# DC_RF_ADDER_single_channel.net
KiCad netlist of a schematic drawn in EAGLE
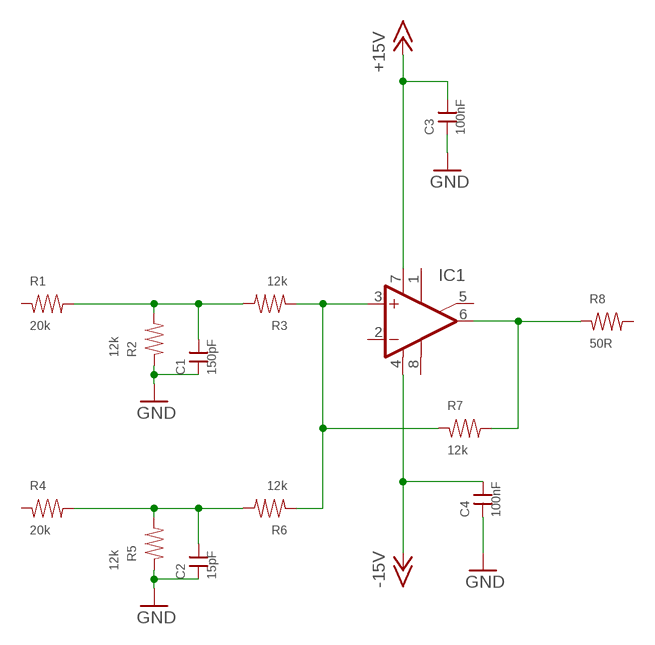
[diagram p0: schematic, sheet 1]

(export (version "E")
  (design (tool "Eeschema 10.0.6"))
  (components
    (comp (ref "C1")
      (value "150pF")
      (footprint "eagle-import:0603")
      (libsource (lib "eagle-import") (part "CAP0603"))
    )
    (comp (ref "C2")
      (value "15pF")
      (footprint "eagle-import:0603")
      (libsource (lib "eagle-import") (part "CAP0603"))
    )
    (comp (ref "C3")
      (value "100nF")
      (footprint "eagle-import:0603")
      (libsource (lib "eagle-import") (part "CAP0603"))
    )
    (comp (ref "C4")
      (value "100nF")
      (footprint "eagle-import:0603")
      (libsource (lib "eagle-import") (part "CAP0603"))
    )
    (comp (ref "IC1")
      (value "OPAMP-SO")
      (footprint "eagle-import:SO08")
      (libsource (lib "eagle-import") (part "OPAMP-SO"))
    )
    (comp (ref "R1")
      (value "20k")
      (footprint "eagle-import:0603")
      (libsource (lib "eagle-import") (part "RES0603"))
    )
    (comp (ref "R2")
      (value "12k")
      (footprint "eagle-import:0603")
      (libsource (lib "eagle-import") (part "RES0603"))
    )
    (comp (ref "R3")
      (value "12k")
      (footprint "eagle-import:0603")
      (libsource (lib "eagle-import") (part "RES0603"))
    )
    (comp (ref "R4")
      (value "20k")
      (footprint "eagle-import:0603")
      (libsource (lib "eagle-import") (part "RES0603"))
    )
    (comp (ref "R5")
      (value "12k")
      (footprint "eagle-import:0603")
      (libsource (lib "eagle-import") (part "RES0603"))
    )
    (comp (ref "R6")
      (value "12k")
      (footprint "eagle-import:0603")
      (libsource (lib "eagle-import") (part "RES0603"))
    )
    (comp (ref "R7")
      (value "12k")
      (footprint "eagle-import:0603")
      (libsource (lib "eagle-import") (part "RES0603"))
    )
    (comp (ref "R8")
      (value "50R")
      (footprint "eagle-import:0603")
      (libsource (lib "eagle-import") (part "RES0603"))
    )
  )
  (nets
    (net (code "1") (name "+15V") (class "Default")
      (node (ref "C3") (pin "2") (pinfunction "P$2_2") (pintype "passive"))
      (node (ref "IC1") (pin "7") (pinfunction "V+_7") (pintype "power_in"))
    )
    (net (code "2") (name "-15V") (class "Default")
      (node (ref "C4") (pin "2") (pinfunction "P$2_2") (pintype "passive"))
      (node (ref "IC1") (pin "4") (pinfunction "V-_4") (pintype "power_in"))
    )
    (net (code "3") (name "GND") (class "Default")
      (node (ref "C1") (pin "1") (pinfunction "P$1_1") (pintype "passive"))
      (node (ref "C2") (pin "1") (pinfunction "P$1_1") (pintype "passive"))
      (node (ref "C3") (pin "1") (pinfunction "P$1_1") (pintype "passive"))
      (node (ref "C4") (pin "1") (pinfunction "P$1_1") (pintype "passive"))
      (node (ref "R2") (pin "1") (pinfunction "P$1_1") (pintype "passive"))
      (node (ref "R5") (pin "1") (pinfunction "P$1_1") (pintype "passive"))
    )
    (net (code "4") (name "Net-(C1-P$2)") (class "Default")
      (node (ref "C1") (pin "2") (pinfunction "P$2_2") (pintype "passive"))
      (node (ref "R1") (pin "2") (pinfunction "P$2_2") (pintype "passive"))
      (node (ref "R2") (pin "2") (pinfunction "P$2_2") (pintype "passive"))
      (node (ref "R3") (pin "2") (pinfunction "P$2_2") (pintype "passive"))
    )
    (net (code "5") (name "Net-(C2-P$2)") (class "Default")
      (node (ref "C2") (pin "2") (pinfunction "P$2_2") (pintype "passive"))
      (node (ref "R4") (pin "2") (pinfunction "P$2_2") (pintype "passive"))
      (node (ref "R5") (pin "2") (pinfunction "P$2_2") (pintype "passive"))
      (node (ref "R6") (pin "2") (pinfunction "P$2_2") (pintype "passive"))
    )
    (net (code "6") (name "Net-(IC1-+IN)") (class "Default")
      (node (ref "IC1") (pin "3") (pinfunction "+IN_3") (pintype "input"))
      (node (ref "R3") (pin "1") (pinfunction "P$1_1") (pintype "passive"))
      (node (ref "R6") (pin "1") (pinfunction "P$1_1") (pintype "passive"))
      (node (ref "R7") (pin "1") (pinfunction "P$1_1") (pintype "passive"))
    )
    (net (code "7") (name "Net-(IC1-OUT)") (class "Default")
      (node (ref "IC1") (pin "6") (pinfunction "OUT_6") (pintype "output"))
      (node (ref "R7") (pin "2") (pinfunction "P$2_2") (pintype "passive"))
      (node (ref "R8") (pin "1") (pinfunction "P$1_1") (pintype "passive"))
    )
    (net (code "8") (name "unconnected-(IC1--IN-Pad2)") (class "Default")
      (node (ref "IC1") (pin "2") (pinfunction "-IN_2") (pintype "input"))
    )
    (net (code "9") (name "unconnected-(IC1-ON1-Pad1)") (class "Default")
      (node (ref "IC1") (pin "1") (pinfunction "ON1_1") (pintype "passive"))
    )
    (net (code "10") (name "unconnected-(IC1-ON2-Pad5)") (class "Default")
      (node (ref "IC1") (pin "5") (pinfunction "ON2_5") (pintype "passive"))
    )
    (net (code "11") (name "unconnected-(IC1-OPT-Pad8)") (class "Default")
      (node (ref "IC1") (pin "8") (pinfunction "OPT_8") (pintype "passive"))
    )
    (net (code "12") (name "unconnected-(R1-P$1-Pad1)") (class "Default")
      (node (ref "R1") (pin "1") (pinfunction "P$1_1") (pintype "passive"))
    )
    (net (code "13") (name "unconnected-(R4-P$1-Pad1)") (class "Default")
      (node (ref "R4") (pin "1") (pinfunction "P$1_1") (pintype "passive"))
    )
    (net (code "14") (name "unconnected-(R8-P$2-Pad2)") (class "Default")
      (node (ref "R8") (pin "2") (pinfunction "P$2_2") (pintype "passive"))
    )
  )
)
